# Keyboard_C64_connector_PCB.net
KiCad netlist of a schematic drawn in EAGLE
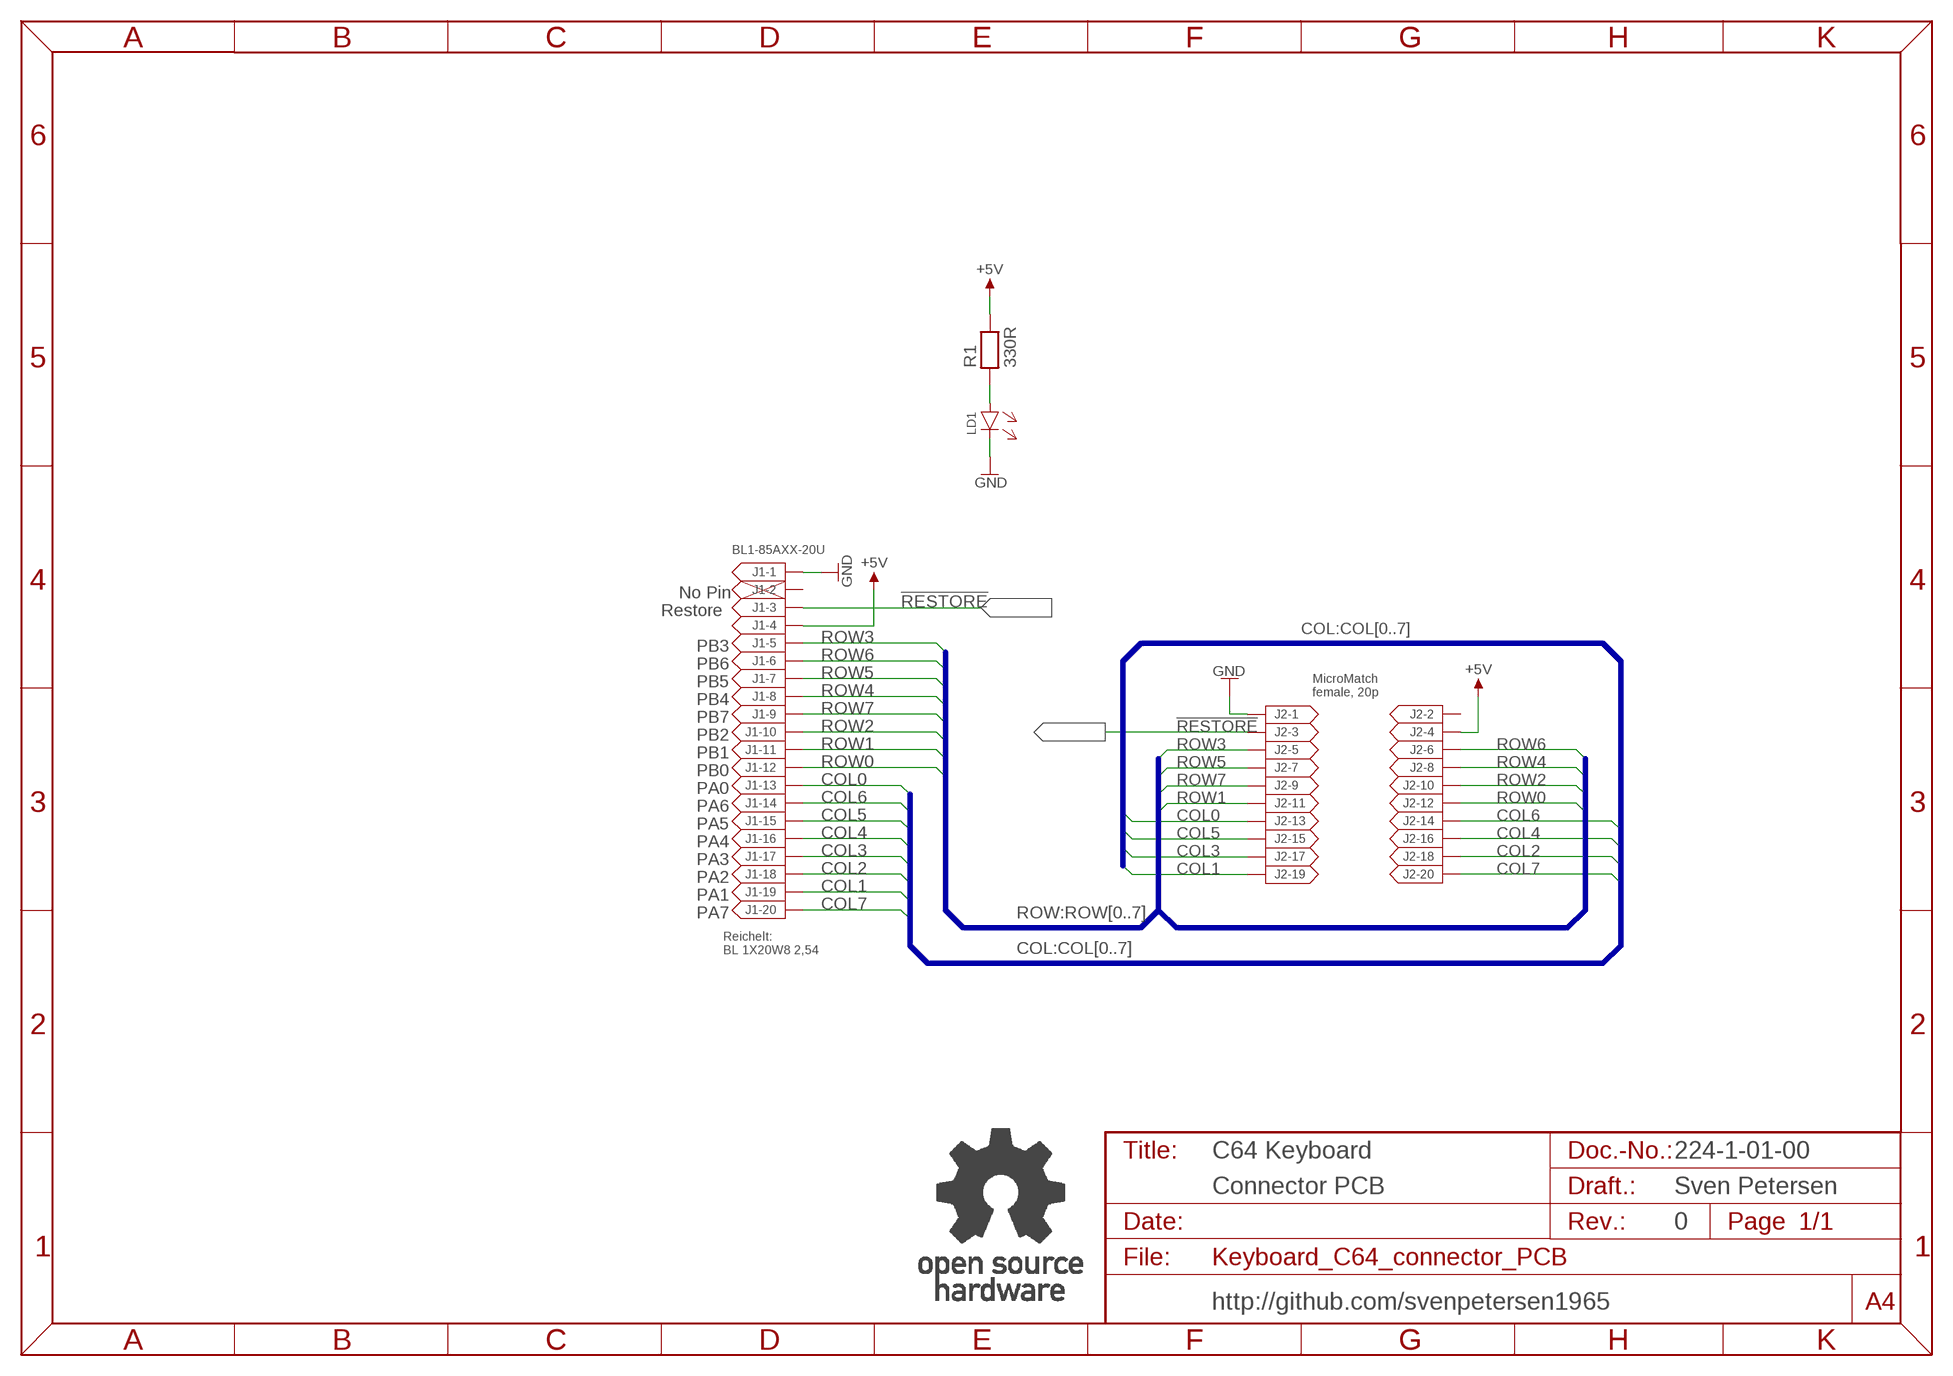
[diagram p0: schematic, sheet 1]

(export (version "E")
  (design (tool "Eeschema 10.0.6"))
  (components
    (comp (ref "J1")
      (value "BL1-85AXX-20U")
      (footprint "eagle-import:BL1-85AXX-20U")
      (libsource (lib "eagle-import") (part "BL1-85AXX-20U"))
    )
    (comp (ref "J2")
      (value "MICMA20B")
      (footprint "eagle-import:MICMA20B")
      (libsource (lib "eagle-import") (part "MICMA20B"))
    )
    (comp (ref "LD1")
      (value "3MM")
      (footprint "eagle-import:3MM")
      (libsource (lib "eagle-import") (part "3MM"))
    )
    (comp (ref "R1")
      (value "330R")
      (footprint "eagle-import:R-10")
      (libsource (lib "eagle-import") (part "RES04"))
    )
    (comp (ref "U$9")
      (value "OPEN_SOURCE_HW")
      (footprint "eagle-import:OPENHW")
      (libsource (lib "eagle-import") (part "OPEN_SOURCE_HW"))
    )
  )
  (nets
    (net (code "17") (name "+5V") (class "Default")
      (node (ref "J1") (pin "4") (pinfunction "1_4") (pintype "bidirectional"))
      (node (ref "J2") (pin "4") (pinfunction "1_4") (pintype "bidirectional"))
      (node (ref "R1") (pin "2") (pinfunction "2_2") (pintype "passive"))
    )
    (net (code "18") (name "/COL0") (class "Default")
      (node (ref "J1") (pin "13") (pinfunction "1_13") (pintype "bidirectional"))
      (node (ref "J2") (pin "13") (pinfunction "1_13") (pintype "bidirectional"))
    )
    (net (code "19") (name "/COL1") (class "Default")
      (node (ref "J1") (pin "19") (pinfunction "1_19") (pintype "bidirectional"))
      (node (ref "J2") (pin "19") (pinfunction "1_19") (pintype "bidirectional"))
    )
    (net (code "20") (name "/COL2") (class "Default")
      (node (ref "J1") (pin "18") (pinfunction "1_18") (pintype "bidirectional"))
      (node (ref "J2") (pin "18") (pinfunction "1_18") (pintype "bidirectional"))
    )
    (net (code "21") (name "/COL3") (class "Default")
      (node (ref "J1") (pin "17") (pinfunction "1_17") (pintype "bidirectional"))
      (node (ref "J2") (pin "17") (pinfunction "1_17") (pintype "bidirectional"))
    )
    (net (code "22") (name "/COL4") (class "Default")
      (node (ref "J1") (pin "16") (pinfunction "1_16") (pintype "bidirectional"))
      (node (ref "J2") (pin "16") (pinfunction "1_16") (pintype "bidirectional"))
    )
    (net (code "23") (name "/COL5") (class "Default")
      (node (ref "J1") (pin "15") (pinfunction "1_15") (pintype "bidirectional"))
      (node (ref "J2") (pin "15") (pinfunction "1_15") (pintype "bidirectional"))
    )
    (net (code "24") (name "/COL6") (class "Default")
      (node (ref "J1") (pin "14") (pinfunction "1_14") (pintype "bidirectional"))
      (node (ref "J2") (pin "14") (pinfunction "1_14") (pintype "bidirectional"))
    )
    (net (code "25") (name "/COL7") (class "Default")
      (node (ref "J1") (pin "20") (pinfunction "1_20") (pintype "bidirectional"))
      (node (ref "J2") (pin "20") (pinfunction "1_20") (pintype "bidirectional"))
    )
    (net (code "27") (name "/ROW0") (class "Default")
      (node (ref "J1") (pin "12") (pinfunction "1_12") (pintype "bidirectional"))
      (node (ref "J2") (pin "12") (pinfunction "1_12") (pintype "bidirectional"))
    )
    (net (code "28") (name "/ROW1") (class "Default")
      (node (ref "J1") (pin "11") (pinfunction "1_11") (pintype "bidirectional"))
      (node (ref "J2") (pin "11") (pinfunction "1_11") (pintype "bidirectional"))
    )
    (net (code "29") (name "/ROW2") (class "Default")
      (node (ref "J1") (pin "10") (pinfunction "1_10") (pintype "bidirectional"))
      (node (ref "J2") (pin "10") (pinfunction "1_10") (pintype "bidirectional"))
    )
    (net (code "30") (name "/ROW3") (class "Default")
      (node (ref "J1") (pin "5") (pinfunction "1_5") (pintype "bidirectional"))
      (node (ref "J2") (pin "5") (pinfunction "1_5") (pintype "bidirectional"))
    )
    (net (code "31") (name "/ROW4") (class "Default")
      (node (ref "J1") (pin "8") (pinfunction "1_8") (pintype "bidirectional"))
      (node (ref "J2") (pin "8") (pinfunction "1_8") (pintype "bidirectional"))
    )
    (net (code "32") (name "/ROW5") (class "Default")
      (node (ref "J1") (pin "7") (pinfunction "1_7") (pintype "bidirectional"))
      (node (ref "J2") (pin "7") (pinfunction "1_7") (pintype "bidirectional"))
    )
    (net (code "33") (name "/ROW6") (class "Default")
      (node (ref "J1") (pin "6") (pinfunction "1_6") (pintype "bidirectional"))
      (node (ref "J2") (pin "6") (pinfunction "1_6") (pintype "bidirectional"))
    )
    (net (code "34") (name "/ROW7") (class "Default")
      (node (ref "J1") (pin "9") (pinfunction "1_9") (pintype "bidirectional"))
      (node (ref "J2") (pin "9") (pinfunction "1_9") (pintype "bidirectional"))
    )
    (net (code "36") (name "/~{RESTORE}") (class "Default")
      (node (ref "J1") (pin "3") (pinfunction "1_3") (pintype "bidirectional"))
      (node (ref "J2") (pin "3") (pinfunction "1_3") (pintype "bidirectional"))
    )
    (net (code "37") (name "GND") (class "Default")
      (node (ref "J1") (pin "1") (pinfunction "1_1") (pintype "bidirectional"))
      (node (ref "J2") (pin "1") (pinfunction "1_1") (pintype "bidirectional"))
      (node (ref "LD1") (pin "C") (pinfunction "K_C") (pintype "bidirectional"))
    )
    (net (code "38") (name "Net-(LD1-PadA)") (class "Default")
      (node (ref "LD1") (pin "A") (pinfunction "A_A") (pintype "bidirectional"))
      (node (ref "R1") (pin "1") (pinfunction "1_1") (pintype "passive"))
    )
    (net (code "39") (name "unconnected-(J1L-1-Pad2)") (class "Default")
      (node (ref "J1") (pin "2") (pinfunction "1_2") (pintype "bidirectional"))
    )
    (net (code "40") (name "unconnected-(J2L-1-Pad2)") (class "Default")
      (node (ref "J2") (pin "2") (pinfunction "1_2") (pintype "bidirectional"))
    )
  )
)
